# CH374.net
KiCad netlist of a schematic drawn in Altium Designer
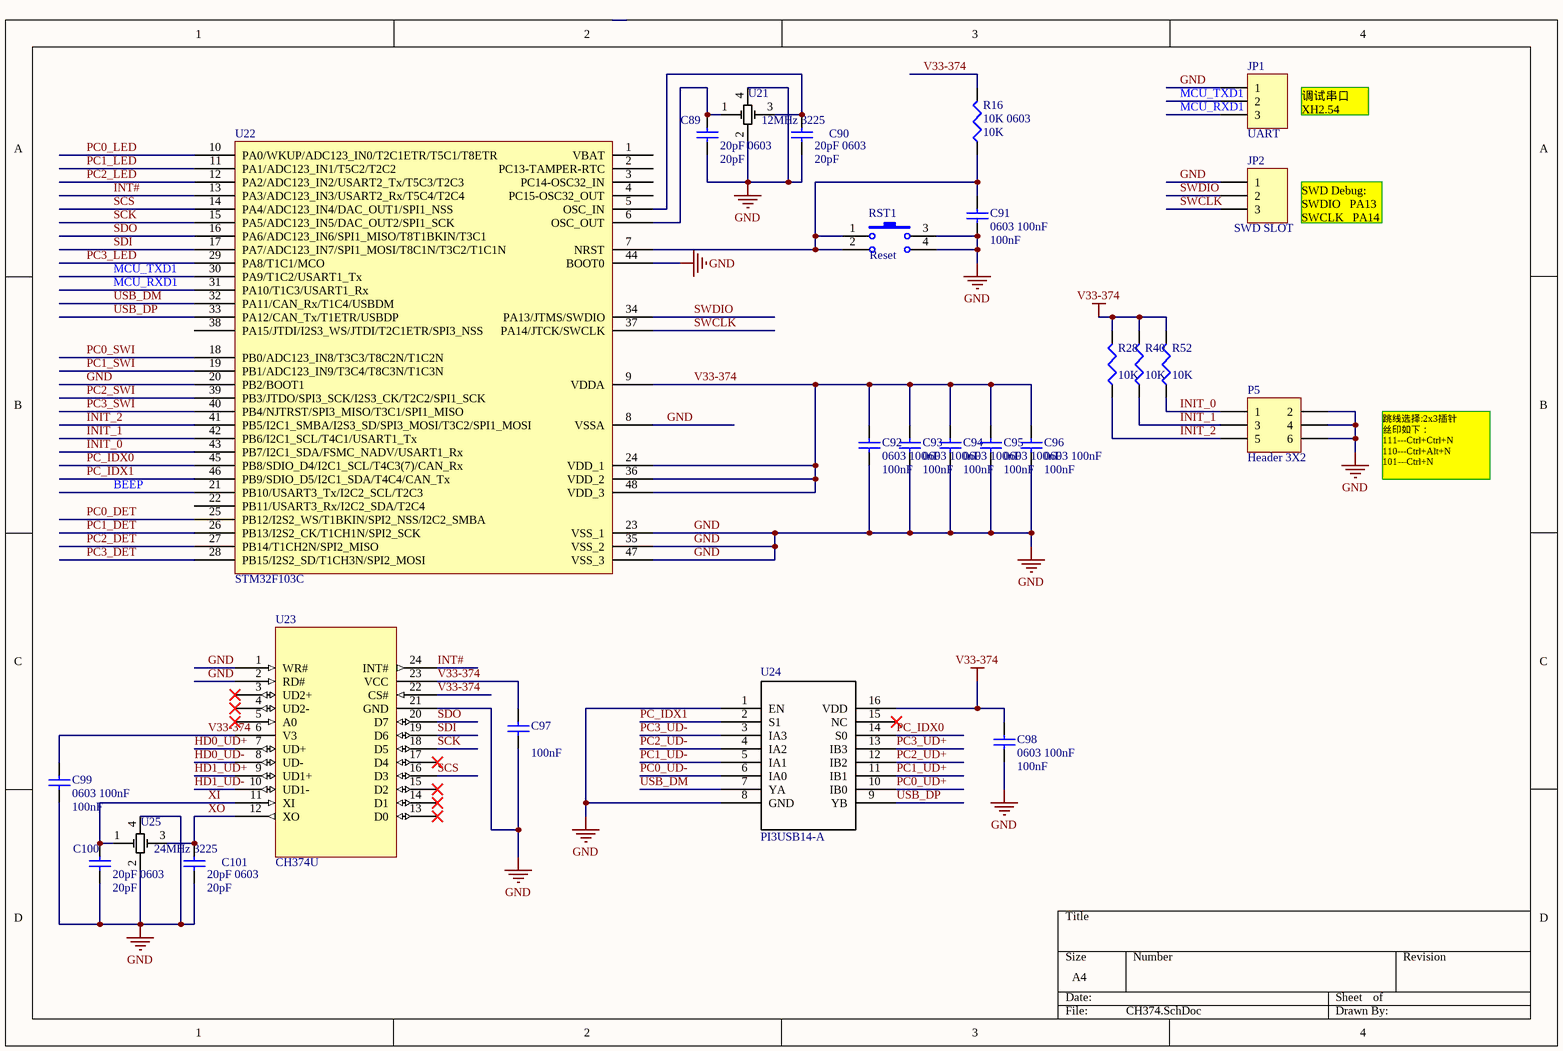
[diagram p0: CH374.SchDoc]

(export (version "E")
  (design (tool "Eeschema 10.0.6"))
  (components
    (comp (ref "C89")
      (value "20pF 0603")
      (footprint "C0603")
      (description "Capacitor (Semiconductor SIM Model)")
      (fields (field (name "ALTIUM_VALUE") "20pF") (field (name "PUBLISHER") "Altium Limited"))
      (libsource (lib "Miscellaneous Devices") (part "Cap Semi"))
    )
    (comp (ref "C90")
      (value "20pF 0603")
      (footprint "C0603")
      (description "Capacitor (Semiconductor SIM Model)")
      (fields (field (name "ALTIUM_VALUE") "20pF") (field (name "PUBLISHER") "Altium Limited"))
      (libsource (lib "Miscellaneous Devices") (part "Cap Semi"))
    )
    (comp (ref "C91")
      (value "0603 100nF")
      (footprint "C0603")
      (description "Capacitor (Semiconductor SIM Model)")
      (fields (field (name "ALTIUM_VALUE") "100nF") (field (name "PUBLISHER") "Altium Limited"))
      (libsource (lib "Miscellaneous Devices") (part "Cap Semi"))
    )
    (comp (ref "C92")
      (value "0603 100nF")
      (footprint "C0603")
      (description "Capacitor (Semiconductor SIM Model)")
      (fields (field (name "ALTIUM_VALUE") "100nF") (field (name "PUBLISHER") "Altium Limited"))
      (libsource (lib "Miscellaneous Devices") (part "Cap Semi"))
    )
    (comp (ref "C93")
      (value "0603 100nF")
      (footprint "C0603")
      (description "Capacitor (Semiconductor SIM Model)")
      (fields (field (name "ALTIUM_VALUE") "100nF") (field (name "PUBLISHER") "Altium Limited"))
      (libsource (lib "Miscellaneous Devices") (part "Cap Semi"))
    )
    (comp (ref "C94")
      (value "0603 100nF")
      (footprint "C0603")
      (description "Capacitor (Semiconductor SIM Model)")
      (fields (field (name "ALTIUM_VALUE") "100nF") (field (name "PUBLISHER") "Altium Limited"))
      (libsource (lib "Miscellaneous Devices") (part "Cap Semi"))
    )
    (comp (ref "C95")
      (value "0603 100nF")
      (footprint "C0603")
      (description "Capacitor (Semiconductor SIM Model)")
      (fields (field (name "ALTIUM_VALUE") "100nF") (field (name "PUBLISHER") "Altium Limited"))
      (libsource (lib "Miscellaneous Devices") (part "Cap Semi"))
    )
    (comp (ref "C96")
      (value "0603 100nF")
      (footprint "C0603")
      (description "Capacitor (Semiconductor SIM Model)")
      (fields (field (name "ALTIUM_VALUE") "100nF") (field (name "PUBLISHER") "Altium Limited"))
      (libsource (lib "Miscellaneous Devices") (part "Cap Semi"))
    )
    (comp (ref "C97")
      (value "100nF")
      (footprint "C0603")
      (description "Capacitor (Semiconductor SIM Model)")
      (fields (field (name "Comment") "0603 100nF") (field (name "PUBLISHER") "Altium Limited"))
      (libsource (lib "Miscellaneous Devices") (part "Cap Semi"))
    )
    (comp (ref "C98")
      (value "0603 100nF")
      (footprint "C0603")
      (description "Capacitor (Semiconductor SIM Model)")
      (fields (field (name "ALTIUM_VALUE") "100nF") (field (name "PUBLISHER") "Altium Limited"))
      (libsource (lib "Miscellaneous Devices") (part "Cap Semi"))
    )
    (comp (ref "C99")
      (value "0603 100nF")
      (footprint "C0603")
      (description "Capacitor (Semiconductor SIM Model)")
      (fields (field (name "ALTIUM_VALUE") "100nF") (field (name "PUBLISHER") "Altium Limited"))
      (libsource (lib "Miscellaneous Devices") (part "Cap Semi"))
    )
    (comp (ref "C100")
      (value "20pF 0603")
      (footprint "C0603")
      (description "Capacitor (Semiconductor SIM Model)")
      (fields (field (name "ALTIUM_VALUE") "20pF") (field (name "PUBLISHER") "Altium Limited"))
      (libsource (lib "Miscellaneous Devices") (part "Cap Semi"))
    )
    (comp (ref "C101")
      (value "20pF 0603")
      (footprint "C0603")
      (description "Capacitor (Semiconductor SIM Model)")
      (fields (field (name "ALTIUM_VALUE") "20pF") (field (name "PUBLISHER") "Altium Limited"))
      (libsource (lib "Miscellaneous Devices") (part "Cap Semi"))
    )
    (comp (ref "JP1")
      (value "UART")
      (footprint "XH25-3")
      (description "Header, 3-Pin")
      (fields (field (name "PUBLISHER") "Altium Limited"))
      (libsource (lib "Header 3") (part "Header 3"))
    )
    (comp (ref "JP2")
      (value "SWD SLOT")
      (footprint "HDR1X3DIP100A")
      (description "Header, 3-Pin")
      (fields (field (name "PUBLISHER") "Altium Limited"))
      (libsource (lib "Header 3") (part "Header 3"))
    )
    (comp (ref "P5")
      (value "Header 3X2")
      (footprint "HDR2X3")
      (description "Header, 3-Pin, Dual row")
      (fields (field (name "PUBLISHER") "Altium Limited"))
      (libsource (lib "Miscellaneous Connectors") (part "Header 3X2"))
    )
    (comp (ref "R16")
      (value "10K 0603")
      (footprint "R0603")
      (description "Resistor")
      (fields (field (name "ALTIUM_VALUE") "10K") (field (name "PUBLISHER") "Altium Limited"))
      (libsource (lib "Miscellaneous Devices") (part "Res3"))
    )
    (comp (ref "R28")
      (value "10K")
      (footprint "R0603")
      (description "Resistor")
      (fields (field (name "Comment") "10K 0603") (field (name "PUBLISHER") "Altium Limited"))
      (libsource (lib "Miscellaneous Devices") (part "Res3"))
    )
    (comp (ref "R40")
      (value "10K")
      (footprint "R0603")
      (description "Resistor")
      (fields (field (name "Comment") "10K 0603") (field (name "PUBLISHER") "Altium Limited"))
      (libsource (lib "Miscellaneous Devices") (part "Res3"))
    )
    (comp (ref "R52")
      (value "10K")
      (footprint "R0603")
      (description "Resistor")
      (fields (field (name "Comment") "10K 0603") (field (name "PUBLISHER") "Altium Limited"))
      (libsource (lib "Miscellaneous Devices") (part "Res3"))
    )
    (comp (ref "RST1")
      (value "Reset")
      (footprint "key_4SMD7351")
      (libsource (lib "key_4smd7351") (part "key_4smd7337"))
    )
    (comp (ref "U21")
      (value "12MHz 3225")
      (footprint "XTAL-3225")
      (libsource (lib "XTAL3225") (part "Component_1"))
    )
    (comp (ref "U22")
      (value "STM32F103C")
      (footprint "QFP48-20-0909B")
      (description "STM32单片机48引脚")
      (libsource (lib "fszhang") (part "STM32F103C"))
    )
    (comp (ref "U23") (value "CH374U") (footprint "SSOP24") (libsource (lib "*") (part "CH374U")))
    (comp (ref "U24")
      (value "PI3USB14-A")
      (footprint "sop16-26-064a")
      (description "Imported")
      (fields (field (name "DESIGNER") "Chiphome"))
      (libsource (lib "USB-new-component") (part "PI3USB14-A"))
    )
    (comp (ref "U25")
      (value "24MHz 3225")
      (footprint "XTAL-3225")
      (libsource (lib "XTAL3225") (part "Component_1"))
    )
  )
  (nets
    (net (code "1") (name "/BEEP") (class "Default")
      (node (ref "U22") (pin "21") (pinfunction "PB10/USART3_Tx/I2C2_SCL/T2C3_21") (pintype "passive"))
    )
    (net (code "2") (name "/HD0_UD+") (class "Default")
      (node (ref "U23") (pin "7") (pinfunction "UD+_7") (pintype "bidirectional"))
    )
    (net (code "3") (name "/HD0_UD-") (class "Default")
      (node (ref "U23") (pin "8") (pinfunction "UD-_8") (pintype "bidirectional"))
    )
    (net (code "4") (name "/HD1_UD+") (class "Default")
      (node (ref "U23") (pin "9") (pinfunction "UD1+_9") (pintype "bidirectional"))
    )
    (net (code "5") (name "/HD1_UD-") (class "Default")
      (node (ref "U23") (pin "10") (pinfunction "UD1-_10") (pintype "bidirectional"))
    )
    (net (code "6") (name "/INIT_0") (class "Default")
      (node (ref "P5") (pin "1") (pinfunction "1_1") (pintype "passive"))
      (node (ref "R52") (pin "1") (pinfunction "1_1") (pintype "passive"))
      (node (ref "U22") (pin "43") (pinfunction "PB7/I2C1_SDA/FSMC_NADV/USART1_Rx_43") (pintype "passive"))
    )
    (net (code "7") (name "/INIT_1") (class "Default")
      (node (ref "P5") (pin "3") (pinfunction "3_3") (pintype "passive"))
      (node (ref "R40") (pin "1") (pinfunction "1_1") (pintype "passive"))
      (node (ref "U22") (pin "42") (pinfunction "PB6/I2C1_SCL/T4C1/USART1_Tx_42") (pintype "passive"))
    )
    (net (code "8") (name "/INIT_2") (class "Default")
      (node (ref "P5") (pin "5") (pinfunction "5_5") (pintype "passive"))
      (node (ref "R28") (pin "1") (pinfunction "1_1") (pintype "passive"))
      (node (ref "U22") (pin "41") (pinfunction "PB5/I2C1_SMBA/I2S3_SD/SPI3_MOSI/T3C2/SPI1_MOSI_41") (pintype "passive"))
    )
    (net (code "9") (name "/INT#") (class "Default")
      (node (ref "U22") (pin "13") (pinfunction "PA3/ADC123_IN3/USART2_Rx/T5C4/T2C4_13") (pintype "passive"))
      (node (ref "U23") (pin "24") (pinfunction "INT#_24") (pintype "output"))
    )
    (net (code "10") (name "/MCU_RXD1") (class "Default")
      (node (ref "JP1") (pin "3") (pinfunction "3_3") (pintype "passive"))
      (node (ref "U22") (pin "31") (pinfunction "PA10/T1C3/USART1_Rx_31") (pintype "passive"))
    )
    (net (code "11") (name "/MCU_TXD1") (class "Default")
      (node (ref "JP1") (pin "2") (pinfunction "2_2") (pintype "passive"))
      (node (ref "U22") (pin "30") (pinfunction "PA9/T1C2/USART1_Tx_30") (pintype "passive"))
    )
    (net (code "12") (name "/PC0_DET") (class "Default")
      (node (ref "U22") (pin "25") (pinfunction "PB12/I2S2_WS/T1BKIN/SPI2_NSS/I2C2_SMBA_25") (pintype "passive"))
    )
    (net (code "13") (name "/PC0_LED") (class "Default")
      (node (ref "U22") (pin "10") (pinfunction "PA0/WKUP/ADC123_IN0/T2C1ETR/T5C1/T8ETR_10") (pintype "passive"))
    )
    (net (code "14") (name "/PC0_SWI") (class "Default")
      (node (ref "U22") (pin "18") (pinfunction "PB0/ADC123_IN8/T3C3/T8C2N/T1C2N_18") (pintype "passive"))
    )
    (net (code "15") (name "/PC0_UD+") (class "Default")
      (node (ref "U24") (pin "10") (pinfunction "IB0_10") (pintype "passive"))
    )
    (net (code "16") (name "/PC0_UD-") (class "Default")
      (node (ref "U24") (pin "6") (pinfunction "IA0_6") (pintype "passive"))
    )
    (net (code "17") (name "/PC1_DET") (class "Default")
      (node (ref "U22") (pin "26") (pinfunction "PB13/I2S2_CK/T1CH1N/SPI2_SCK_26") (pintype "passive"))
    )
    (net (code "18") (name "/PC1_LED") (class "Default")
      (node (ref "U22") (pin "11") (pinfunction "PA1/ADC123_IN1/T5C2/T2C2_11") (pintype "passive"))
    )
    (net (code "19") (name "/PC1_SWI") (class "Default")
      (node (ref "U22") (pin "19") (pinfunction "PB1/ADC123_IN9/T3C4/T8C3N/T1C3N_19") (pintype "passive"))
    )
    (net (code "20") (name "/PC1_UD+") (class "Default")
      (node (ref "U24") (pin "11") (pinfunction "IB1_11") (pintype "passive"))
    )
    (net (code "21") (name "/PC1_UD-") (class "Default")
      (node (ref "U24") (pin "5") (pinfunction "IA1_5") (pintype "passive"))
    )
    (net (code "22") (name "/PC2_DET") (class "Default")
      (node (ref "U22") (pin "27") (pinfunction "PB14/T1CH2N/SPI2_MISO_27") (pintype "passive"))
    )
    (net (code "23") (name "/PC2_LED") (class "Default")
      (node (ref "U22") (pin "12") (pinfunction "PA2/ADC123_IN2/USART2_Tx/T5C3/T2C3_12") (pintype "passive"))
    )
    (net (code "24") (name "/PC2_SWI") (class "Default")
      (node (ref "U22") (pin "39") (pinfunction "PB3/JTDO/SPI3_SCK/I2S3_CK/T2C2/SPI1_SCK_39") (pintype "passive"))
    )
    (net (code "25") (name "/PC2_UD+") (class "Default")
      (node (ref "U24") (pin "12") (pinfunction "IB2_12") (pintype "passive"))
    )
    (net (code "26") (name "/PC2_UD-") (class "Default")
      (node (ref "U24") (pin "4") (pinfunction "IA2_4") (pintype "passive"))
    )
    (net (code "27") (name "/PC3_DET") (class "Default")
      (node (ref "U22") (pin "28") (pinfunction "PB15/I2S2_SD/T1CH3N/SPI2_MOSI_28") (pintype "passive"))
    )
    (net (code "28") (name "/PC3_LED") (class "Default")
      (node (ref "U22") (pin "29") (pinfunction "PA8/T1C1/MCO_29") (pintype "passive"))
    )
    (net (code "29") (name "/PC3_SWI") (class "Default")
      (node (ref "U22") (pin "40") (pinfunction "PB4/NJTRST/SPI3_MISO/T3C1/SPI1_MISO_40") (pintype "passive"))
    )
    (net (code "30") (name "/PC3_UD+") (class "Default")
      (node (ref "U24") (pin "13") (pinfunction "IB3_13") (pintype "passive"))
    )
    (net (code "31") (name "/PC3_UD-") (class "Default")
      (node (ref "U24") (pin "3") (pinfunction "IA3_3") (pintype "passive"))
    )
    (net (code "32") (name "/PC_IDX0") (class "Default")
      (node (ref "U22") (pin "45") (pinfunction "PB8/SDIO_D4/I2C1_SCL/T4C3(7)/CAN_Rx_45") (pintype "passive"))
      (node (ref "U24") (pin "14") (pinfunction "S0_14") (pintype "passive"))
    )
    (net (code "33") (name "/PC_IDX1") (class "Default")
      (node (ref "U22") (pin "46") (pinfunction "PB9/SDIO_D5/I2C1_SDA/T4C4/CAN_Tx_46") (pintype "passive"))
      (node (ref "U24") (pin "2") (pinfunction "S1_2") (pintype "passive"))
    )
    (net (code "34") (name "/SCK") (class "Default")
      (node (ref "U22") (pin "15") (pinfunction "PA5/ADC123_IN5/DAC_OUT2/SPI1_SCK_15") (pintype "passive"))
      (node (ref "U23") (pin "18") (pinfunction "D5_18") (pintype "bidirectional"))
    )
    (net (code "35") (name "/SCS") (class "Default")
      (node (ref "U22") (pin "14") (pinfunction "PA4/ADC123_IN4/DAC_OUT1/SPI1_NSS_14") (pintype "passive"))
      (node (ref "U23") (pin "16") (pinfunction "D3_16") (pintype "bidirectional"))
    )
    (net (code "36") (name "/SDI") (class "Default")
      (node (ref "U22") (pin "17") (pinfunction "PA7/ADC123_IN7/SPI1_MOSI/T8C1N/T3C2/T1C1N_17") (pintype "passive"))
      (node (ref "U23") (pin "19") (pinfunction "D6_19") (pintype "bidirectional"))
    )
    (net (code "37") (name "/SDO") (class "Default")
      (node (ref "U22") (pin "16") (pinfunction "PA6/ADC123_IN6/SPI1_MISO/T8T1BKIN/T3C1_16") (pintype "passive"))
      (node (ref "U23") (pin "20") (pinfunction "D7_20") (pintype "bidirectional"))
    )
    (net (code "38") (name "/SWCLK") (class "Default")
      (node (ref "JP2") (pin "3") (pinfunction "3_3") (pintype "passive"))
      (node (ref "U22") (pin "37") (pinfunction "PA14/JTCK/SWCLK_37") (pintype "passive"))
    )
    (net (code "39") (name "/SWDIO") (class "Default")
      (node (ref "JP2") (pin "2") (pinfunction "2_2") (pintype "passive"))
      (node (ref "U22") (pin "34") (pinfunction "PA13/JTMS/SWDIO_34") (pintype "passive"))
    )
    (net (code "40") (name "/USB_DM") (class "Default")
      (node (ref "U22") (pin "32") (pinfunction "PA11/CAN_Rx/T1C4/USBDM_32") (pintype "passive"))
      (node (ref "U24") (pin "7") (pinfunction "YA_7") (pintype "passive"))
    )
    (net (code "41") (name "/USB_DP") (class "Default")
      (node (ref "U22") (pin "33") (pinfunction "PA12/CAN_Tx/T1ETR/USBDP_33") (pintype "passive"))
      (node (ref "U24") (pin "9") (pinfunction "YB_9") (pintype "passive"))
    )
    (net (code "42") (name "/XI") (class "Default")
      (node (ref "C100") (pin "2") (pinfunction "2_2") (pintype "passive"))
      (node (ref "U23") (pin "11") (pinfunction "XI_11") (pintype "input"))
      (node (ref "U25") (pin "1") (pinfunction "1_1") (pintype "passive"))
    )
    (net (code "43") (name "/XO") (class "Default")
      (node (ref "C101") (pin "2") (pinfunction "2_2") (pintype "passive"))
      (node (ref "U23") (pin "12") (pinfunction "XO_12") (pintype "output"))
      (node (ref "U25") (pin "3") (pinfunction "3_3") (pintype "passive"))
    )
    (net (code "44") (name "GND") (class "Default")
      (node (ref "C100") (pin "1") (pinfunction "1_1") (pintype "passive"))
      (node (ref "C101") (pin "1") (pinfunction "1_1") (pintype "passive"))
      (node (ref "C89") (pin "1") (pinfunction "1_1") (pintype "passive"))
      (node (ref "C90") (pin "1") (pinfunction "1_1") (pintype "passive"))
      (node (ref "C91") (pin "1") (pinfunction "1_1") (pintype "passive"))
      (node (ref "C92") (pin "1") (pinfunction "1_1") (pintype "passive"))
      (node (ref "C93") (pin "1") (pinfunction "1_1") (pintype "passive"))
      (node (ref "C94") (pin "1") (pinfunction "1_1") (pintype "passive"))
      (node (ref "C95") (pin "1") (pinfunction "1_1") (pintype "passive"))
      (node (ref "C96") (pin "1") (pinfunction "1_1") (pintype "passive"))
      (node (ref "C97") (pin "1") (pinfunction "1_1") (pintype "passive"))
      (node (ref "C98") (pin "1") (pinfunction "1_1") (pintype "passive"))
      (node (ref "C99") (pin "1") (pinfunction "1_1") (pintype "passive"))
      (node (ref "JP1") (pin "1") (pinfunction "1_1") (pintype "passive"))
      (node (ref "JP2") (pin "1") (pinfunction "1_1") (pintype "passive"))
      (node (ref "P5") (pin "2") (pinfunction "2_2") (pintype "passive"))
      (node (ref "P5") (pin "4") (pinfunction "4_4") (pintype "passive"))
      (node (ref "P5") (pin "6") (pinfunction "6_6") (pintype "passive"))
      (node (ref "RST1") (pin "3") (pinfunction "3_3") (pintype "passive"))
      (node (ref "RST1") (pin "4") (pinfunction "4_4") (pintype "passive"))
      (node (ref "U21") (pin "2") (pinfunction "2_2") (pintype "passive"))
      (node (ref "U21") (pin "4") (pinfunction "4_4") (pintype "passive"))
      (node (ref "U22") (pin "20") (pinfunction "PB2/BOOT1_20") (pintype "passive"))
      (node (ref "U22") (pin "23") (pinfunction "VSS_1_23") (pintype "passive"))
      (node (ref "U22") (pin "35") (pinfunction "VSS_2_35") (pintype "passive"))
      (node (ref "U22") (pin "44") (pinfunction "BOOT0_44") (pintype "passive"))
      (node (ref "U22") (pin "47") (pinfunction "VSS_3_47") (pintype "passive"))
      (node (ref "U22") (pin "8") (pinfunction "VSSA_8") (pintype "passive"))
      (node (ref "U23") (pin "1") (pinfunction "WR#_1") (pintype "input"))
      (node (ref "U23") (pin "2") (pinfunction "RD#_2") (pintype "input"))
      (node (ref "U23") (pin "21") (pinfunction "GND_21") (pintype "power_in"))
      (node (ref "U24") (pin "1") (pinfunction "EN_1") (pintype "passive"))
      (node (ref "U24") (pin "8") (pinfunction "GND_8") (pintype "passive"))
      (node (ref "U25") (pin "2") (pinfunction "2_2") (pintype "passive"))
      (node (ref "U25") (pin "4") (pinfunction "4_4") (pintype "passive"))
    )
    (net (code "45") (name "Net-(U22-NRST)") (class "Default")
      (node (ref "C91") (pin "2") (pinfunction "2_2") (pintype "passive"))
      (node (ref "R16") (pin "1") (pinfunction "1_1") (pintype "passive"))
      (node (ref "RST1") (pin "1") (pinfunction "1_1") (pintype "passive"))
      (node (ref "RST1") (pin "2") (pinfunction "2_2") (pintype "passive"))
      (node (ref "U22") (pin "7") (pinfunction "NRST_7") (pintype "passive"))
    )
    (net (code "46") (name "Net-(U22-OSC_IN)") (class "Default")
      (node (ref "C90") (pin "2") (pinfunction "2_2") (pintype "passive"))
      (node (ref "U21") (pin "3") (pinfunction "3_3") (pintype "passive"))
      (node (ref "U22") (pin "5") (pinfunction "OSC_IN_5") (pintype "passive"))
    )
    (net (code "47") (name "Net-(U22-OSC_OUT)") (class "Default")
      (node (ref "C89") (pin "2") (pinfunction "2_2") (pintype "passive"))
      (node (ref "U21") (pin "1") (pinfunction "1_1") (pintype "passive"))
      (node (ref "U22") (pin "6") (pinfunction "OSC_OUT_6") (pintype "passive"))
    )
    (net (code "48") (name "V33-374") (class "Default")
      (node (ref "C92") (pin "2") (pinfunction "2_2") (pintype "passive"))
      (node (ref "C93") (pin "2") (pinfunction "2_2") (pintype "passive"))
      (node (ref "C94") (pin "2") (pinfunction "2_2") (pintype "passive"))
      (node (ref "C95") (pin "2") (pinfunction "2_2") (pintype "passive"))
      (node (ref "C96") (pin "2") (pinfunction "2_2") (pintype "passive"))
      (node (ref "C97") (pin "2") (pinfunction "2_2") (pintype "passive"))
      (node (ref "C98") (pin "2") (pinfunction "2_2") (pintype "passive"))
      (node (ref "C99") (pin "2") (pinfunction "2_2") (pintype "passive"))
      (node (ref "R16") (pin "2") (pinfunction "2_2") (pintype "passive"))
      (node (ref "R28") (pin "2") (pinfunction "2_2") (pintype "passive"))
      (node (ref "R40") (pin "2") (pinfunction "2_2") (pintype "passive"))
      (node (ref "R52") (pin "2") (pinfunction "2_2") (pintype "passive"))
      (node (ref "U22") (pin "24") (pinfunction "VDD_1_24") (pintype "passive"))
      (node (ref "U22") (pin "36") (pinfunction "VDD_2_36") (pintype "passive"))
      (node (ref "U22") (pin "48") (pinfunction "VDD_3_48") (pintype "passive"))
      (node (ref "U22") (pin "9") (pinfunction "VDDA_9") (pintype "passive"))
      (node (ref "U23") (pin "22") (pinfunction "CS#_22") (pintype "input"))
      (node (ref "U23") (pin "23") (pinfunction "VCC_23") (pintype "power_in"))
      (node (ref "U23") (pin "6") (pinfunction "V3_6") (pintype "power_in"))
      (node (ref "U24") (pin "16") (pinfunction "VDD_16") (pintype "passive"))
    )
    (net (code "49") (name "unconnected-(U22-PA15{slash}JTDI{slash}I2S3_WS{slash}JTDI{slash}T2C1ETR{slash}SPI3_NSS-Pad38)") (class "Default")
      (node (ref "U22") (pin "38") (pinfunction "PA15/JTDI/I2S3_WS/JTDI/T2C1ETR/SPI3_NSS_38") (pintype "passive"))
    )
    (net (code "50") (name "unconnected-(U22-PB11{slash}USART3_Rx{slash}I2C2_SDA{slash}T2C4-Pad22)") (class "Default")
      (node (ref "U22") (pin "22") (pinfunction "PB11/USART3_Rx/I2C2_SDA/T2C4_22") (pintype "passive"))
    )
    (net (code "51") (name "unconnected-(U22-PC13-TAMPER-RTC-Pad2)") (class "Default")
      (node (ref "U22") (pin "2") (pinfunction "PC13-TAMPER-RTC_2") (pintype "passive"))
    )
    (net (code "52") (name "unconnected-(U22-PC14-OSC32_IN-Pad3)") (class "Default")
      (node (ref "U22") (pin "3") (pinfunction "PC14-OSC32_IN_3") (pintype "passive"))
    )
    (net (code "53") (name "unconnected-(U22-PC15-OSC32_OUT-Pad4)") (class "Default")
      (node (ref "U22") (pin "4") (pinfunction "PC15-OSC32_OUT_4") (pintype "passive"))
    )
    (net (code "54") (name "unconnected-(U22-VBAT-Pad1)") (class "Default")
      (node (ref "U22") (pin "1") (pinfunction "VBAT_1") (pintype "passive"))
    )
    (net (code "55") (name "unconnected-(U23-A0-Pad5)") (class "Default")
      (node (ref "U23") (pin "5") (pinfunction "A0_5") (pintype "input+no_connect"))
    )
    (net (code "56") (name "unconnected-(U23-D0-Pad13)") (class "Default")
      (node (ref "U23") (pin "13") (pinfunction "D0_13") (pintype "bidirectional+no_connect"))
    )
    (net (code "57") (name "unconnected-(U23-D1-Pad14)") (class "Default")
      (node (ref "U23") (pin "14") (pinfunction "D1_14") (pintype "bidirectional+no_connect"))
    )
    (net (code "58") (name "unconnected-(U23-D2-Pad15)") (class "Default")
      (node (ref "U23") (pin "15") (pinfunction "D2_15") (pintype "bidirectional+no_connect"))
    )
    (net (code "59") (name "unconnected-(U23-D4-Pad17)") (class "Default")
      (node (ref "U23") (pin "17") (pinfunction "D4_17") (pintype "bidirectional+no_connect"))
    )
    (net (code "60") (name "unconnected-(U23-UD2+-Pad3)") (class "Default")
      (node (ref "U23") (pin "3") (pinfunction "UD2+_3") (pintype "bidirectional+no_connect"))
    )
    (net (code "61") (name "unconnected-(U23-UD2--Pad4)") (class "Default")
      (node (ref "U23") (pin "4") (pinfunction "UD2-_4") (pintype "bidirectional+no_connect"))
    )
    (net (code "62") (name "unconnected-(U24-NC-Pad15)") (class "Default")
      (node (ref "U24") (pin "15") (pinfunction "NC_15") (pintype "passive+no_connect"))
    )
  )
)
